# ovtave_up_pcbv1_5.net
KiCad netlist of a schematic drawn in EAGLE
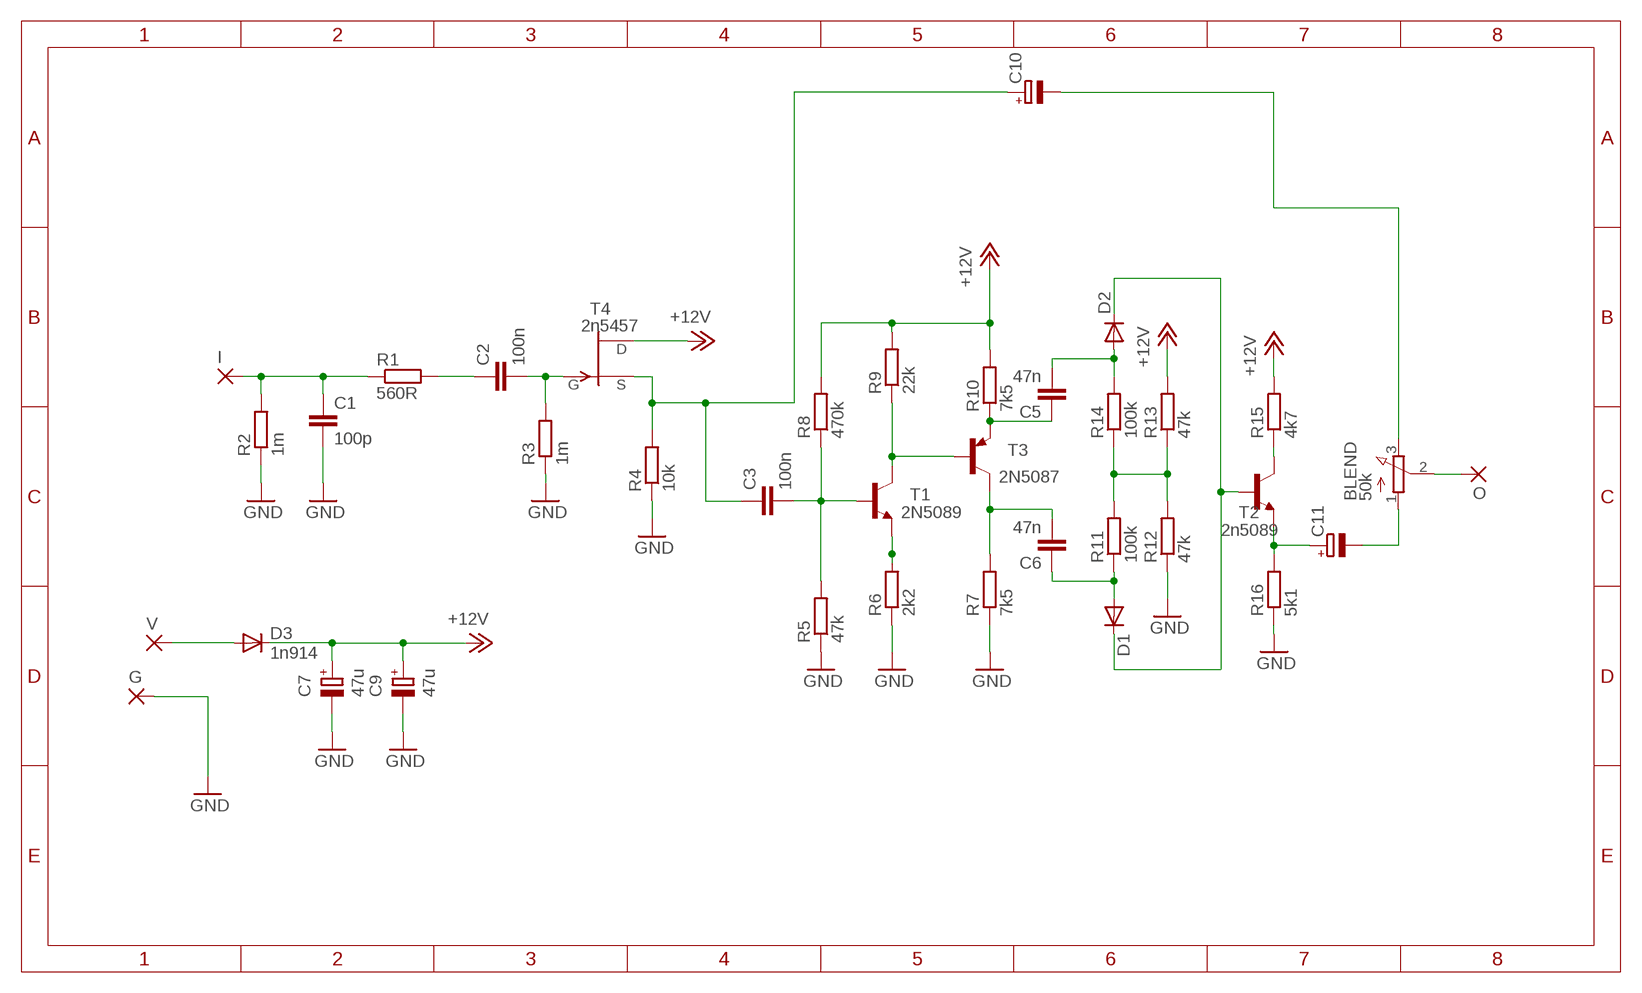
[diagram p0: schematic, sheet 1]

(export (version "E")
  (design (tool "Eeschema 10.0.6"))
  (components
    (comp (ref "BLEND")
      (value "50k")
      (footprint "eagle-import:3RP_1610N")
      (libsource (lib "eagle-import") (part "HEXPOT1"))
    )
    (comp (ref "C1")
      (value "100p")
      (footprint "eagle-import:C5B2.5")
      (libsource (lib "eagle-import") (part "C5/2.5"))
    )
    (comp (ref "C2")
      (value "100n")
      (footprint "eagle-import:C5B2.5")
      (libsource (lib "eagle-import") (part "C5/2.5"))
    )
    (comp (ref "C3")
      (value "100n")
      (footprint "eagle-import:C5B2.5")
      (libsource (lib "eagle-import") (part "C5/2.5"))
    )
    (comp (ref "C5")
      (value "47n")
      (footprint "eagle-import:C5B2.5")
      (libsource (lib "eagle-import") (part "C5/2.5"))
    )
    (comp (ref "C6")
      (value "47n")
      (footprint "eagle-import:C5B2.5")
      (libsource (lib "eagle-import") (part "C5/2.5"))
    )
    (comp (ref "C7")
      (value "47u")
      (footprint "eagle-import:E2-4")
      (libsource (lib "eagle-import") (part "rcl_334_CPOL-EUE2-4"))
    )
    (comp (ref "C9")
      (value "47u")
      (footprint "eagle-import:E2-4")
      (libsource (lib "eagle-import") (part "rcl_334_CPOL-EUE2-4"))
    )
    (comp (ref "C10")
      (value "CPOL-EUE2-4")
      (footprint "eagle-import:E2-4")
      (libsource (lib "eagle-import") (part "CPOL-EUE2-4"))
    )
    (comp (ref "C11")
      (value "CPOL-EUE2-4")
      (footprint "eagle-import:E2-4")
      (libsource (lib "eagle-import") (part "CPOL-EUE2-4"))
    )
    (comp (ref "D1")
      (value "Ge fV match")
      (footprint "eagle-import:DO35-7")
      (libsource (lib "eagle-import") (part "SMALL_DIODEDO35-7"))
    )
    (comp (ref "D2")
      (value "Ge fV match")
      (footprint "eagle-import:DO35-7")
      (libsource (lib "eagle-import") (part "SMALL_DIODEDO35-7"))
    )
    (comp (ref "D3")
      (value "1n914")
      (footprint "eagle-import:DO35-7")
      (libsource (lib "eagle-import") (part "SMALL_DIODEDO35-7"))
    )
    (comp (ref "G")
      (value "1,6/0,9")
      (footprint "eagle-import:1,6_0,9")
      (libsource (lib "eagle-import") (part "1,6/0,9"))
    )
    (comp (ref "I")
      (value "1,6/0,9")
      (footprint "eagle-import:1,6_0,9")
      (libsource (lib "eagle-import") (part "1,6/0,9"))
    )
    (comp (ref "O")
      (value "1,6/0,9")
      (footprint "eagle-import:1,6_0,9")
      (libsource (lib "eagle-import") (part "1,6/0,9"))
    )
    (comp (ref "R1")
      (value "560R")
      (footprint "eagle-import:0207_7")
      (libsource (lib "eagle-import") (part "R-EU_0207/7"))
    )
    (comp (ref "R2")
      (value "1m")
      (footprint "eagle-import:0207_7")
      (libsource (lib "eagle-import") (part "R-EU_0207/7"))
    )
    (comp (ref "R3")
      (value "1m")
      (footprint "eagle-import:0207_7")
      (libsource (lib "eagle-import") (part "R-EU_0207/7"))
    )
    (comp (ref "R4")
      (value "10k")
      (footprint "eagle-import:0207_7")
      (libsource (lib "eagle-import") (part "R-EU_0207/7"))
    )
    (comp (ref "R5")
      (value "47k")
      (footprint "eagle-import:0207_7")
      (libsource (lib "eagle-import") (part "R-EU_0207/7"))
    )
    (comp (ref "R6")
      (value "2k2")
      (footprint "eagle-import:0207_7")
      (libsource (lib "eagle-import") (part "R-EU_0207/7"))
    )
    (comp (ref "R7")
      (value "7k5")
      (footprint "eagle-import:0207_7")
      (libsource (lib "eagle-import") (part "R-EU_0207/7"))
    )
    (comp (ref "R8")
      (value "470k")
      (footprint "eagle-import:0207_7")
      (libsource (lib "eagle-import") (part "R-EU_0207/7"))
    )
    (comp (ref "R9")
      (value "22k")
      (footprint "eagle-import:0207_7")
      (libsource (lib "eagle-import") (part "R-EU_0207/7"))
    )
    (comp (ref "R10")
      (value "7k5")
      (footprint "eagle-import:0207_7")
      (libsource (lib "eagle-import") (part "R-EU_0207/7"))
    )
    (comp (ref "R11")
      (value "100k")
      (footprint "eagle-import:0207_7")
      (libsource (lib "eagle-import") (part "R-EU_0207/7"))
    )
    (comp (ref "R12")
      (value "47k")
      (footprint "eagle-import:0207_7")
      (libsource (lib "eagle-import") (part "R-EU_0207/7"))
    )
    (comp (ref "R13")
      (value "47k")
      (footprint "eagle-import:0207_7")
      (libsource (lib "eagle-import") (part "R-EU_0207/7"))
    )
    (comp (ref "R14")
      (value "100k")
      (footprint "eagle-import:0207_7")
      (libsource (lib "eagle-import") (part "R-EU_0207/7"))
    )
    (comp (ref "R15")
      (value "4k7")
      (footprint "eagle-import:0207_7")
      (libsource (lib "eagle-import") (part "R-EU_0207/7"))
    )
    (comp (ref "R16")
      (value "5k1")
      (footprint "eagle-import:0207_7")
      (libsource (lib "eagle-import") (part "R-EU_0207/7"))
    )
    (comp (ref "T1")
      (value "2N5089")
      (footprint "eagle-import:TO92")
      (libsource (lib "eagle-import") (part "2N5089"))
    )
    (comp (ref "T2")
      (value "2n5089")
      (footprint "eagle-import:TO92")
      (libsource (lib "eagle-import") (part "2N5089"))
    )
    (comp (ref "T3")
      (value "2N5087")
      (footprint "eagle-import:TO92")
      (libsource (lib "eagle-import") (part "2N5087"))
    )
    (comp (ref "T4")
      (value "2n5457")
      (footprint "eagle-import:TO92")
      (libsource (lib "eagle-import") (part "?20J1"))
    )
    (comp (ref "V")
      (value "1,6/0,9")
      (footprint "eagle-import:1,6_0,9")
      (libsource (lib "eagle-import") (part "1,6/0,9"))
    )
  )
  (nets
    (net (code "1") (name "+12V") (class "Default")
      (node (ref "C7") (pin "+") (pinfunction "+_+") (pintype "passive"))
      (node (ref "C9") (pin "+") (pinfunction "+_+") (pintype "passive"))
      (node (ref "D3") (pin "C") (pinfunction "C_C") (pintype "passive"))
      (node (ref "R10") (pin "2") (pinfunction "2_2") (pintype "passive"))
      (node (ref "R13") (pin "2") (pinfunction "2_2") (pintype "passive"))
      (node (ref "R15") (pin "2") (pinfunction "2_2") (pintype "passive"))
      (node (ref "R8") (pin "2") (pinfunction "2_2") (pintype "passive"))
      (node (ref "R9") (pin "2") (pinfunction "2_2") (pintype "passive"))
      (node (ref "T4") (pin "3") (pinfunction "D_3") (pintype "passive"))
    )
    (net (code "2") (name "GND") (class "Default")
      (node (ref "C1") (pin "2") (pinfunction "2_2") (pintype "passive"))
      (node (ref "C7") (pin "-") (pinfunction "-_-") (pintype "passive"))
      (node (ref "C9") (pin "-") (pinfunction "-_-") (pintype "passive"))
      (node (ref "G") (pin "1") (pinfunction "P_1") (pintype "passive"))
      (node (ref "R12") (pin "1") (pinfunction "1_1") (pintype "passive"))
      (node (ref "R16") (pin "1") (pinfunction "1_1") (pintype "passive"))
      (node (ref "R2") (pin "1") (pinfunction "1_1") (pintype "passive"))
      (node (ref "R3") (pin "1") (pinfunction "1_1") (pintype "passive"))
      (node (ref "R4") (pin "1") (pinfunction "1_1") (pintype "passive"))
      (node (ref "R5") (pin "1") (pinfunction "1_1") (pintype "passive"))
      (node (ref "R6") (pin "1") (pinfunction "1_1") (pintype "passive"))
      (node (ref "R7") (pin "1") (pinfunction "1_1") (pintype "passive"))
    )
    (net (code "3") (name "Net-(BLEND-A)") (class "Default")
      (node (ref "BLEND") (pin "1") (pinfunction "A_1") (pintype "passive"))
      (node (ref "C11") (pin "-") (pinfunction "-_-") (pintype "passive"))
    )
    (net (code "4") (name "Net-(BLEND-E)") (class "Default")
      (node (ref "BLEND") (pin "3") (pinfunction "E_3") (pintype "passive"))
      (node (ref "C10") (pin "-") (pinfunction "-_-") (pintype "passive"))
    )
    (net (code "5") (name "Net-(BLEND-S)") (class "Default")
      (node (ref "BLEND") (pin "2") (pinfunction "S_2") (pintype "passive"))
      (node (ref "O") (pin "1") (pinfunction "P_1") (pintype "passive"))
    )
    (net (code "6") (name "Net-(C2-Pad1)") (class "Default")
      (node (ref "C2") (pin "1") (pinfunction "1_1") (pintype "passive"))
      (node (ref "R1") (pin "2") (pinfunction "2_2") (pintype "passive"))
    )
    (net (code "7") (name "Net-(C5-Pad2)") (class "Default")
      (node (ref "C5") (pin "2") (pinfunction "2_2") (pintype "passive"))
      (node (ref "D2") (pin "A") (pinfunction "A_A") (pintype "passive"))
      (node (ref "R14") (pin "2") (pinfunction "2_2") (pintype "passive"))
    )
    (net (code "8") (name "Net-(C6-Pad1)") (class "Default")
      (node (ref "C6") (pin "1") (pinfunction "1_1") (pintype "passive"))
      (node (ref "D1") (pin "A") (pinfunction "A_A") (pintype "passive"))
      (node (ref "R11") (pin "1") (pinfunction "1_1") (pintype "passive"))
    )
    (net (code "9") (name "Net-(I-P)") (class "Default")
      (node (ref "C1") (pin "1") (pinfunction "1_1") (pintype "passive"))
      (node (ref "I") (pin "1") (pinfunction "P_1") (pintype "passive"))
      (node (ref "R1") (pin "1") (pinfunction "1_1") (pintype "passive"))
      (node (ref "R2") (pin "2") (pinfunction "2_2") (pintype "passive"))
    )
    (net (code "10") (name "Net-(R11-Pad2)") (class "Default")
      (node (ref "R11") (pin "2") (pinfunction "2_2") (pintype "passive"))
      (node (ref "R12") (pin "2") (pinfunction "2_2") (pintype "passive"))
      (node (ref "R13") (pin "1") (pinfunction "1_1") (pintype "passive"))
      (node (ref "R14") (pin "1") (pinfunction "1_1") (pintype "passive"))
    )
    (net (code "11") (name "Net-(T1-B)") (class "Default")
      (node (ref "C3") (pin "2") (pinfunction "2_2") (pintype "passive"))
      (node (ref "R5") (pin "2") (pinfunction "2_2") (pintype "passive"))
      (node (ref "R8") (pin "1") (pinfunction "1_1") (pintype "passive"))
      (node (ref "T1") (pin "2") (pinfunction "B_2") (pintype "passive"))
    )
    (net (code "12") (name "Net-(T1-C)") (class "Default")
      (node (ref "R9") (pin "1") (pinfunction "1_1") (pintype "passive"))
      (node (ref "T1") (pin "1") (pinfunction "C_1") (pintype "passive"))
      (node (ref "T3") (pin "2") (pinfunction "B_2") (pintype "passive"))
    )
    (net (code "13") (name "Net-(T1-E)") (class "Default")
      (node (ref "R6") (pin "2") (pinfunction "2_2") (pintype "passive"))
      (node (ref "T1") (pin "3") (pinfunction "E_3") (pintype "passive"))
    )
    (net (code "14") (name "Net-(T2-B)") (class "Default")
      (node (ref "D1") (pin "C") (pinfunction "C_C") (pintype "passive"))
      (node (ref "D2") (pin "C") (pinfunction "C_C") (pintype "passive"))
      (node (ref "T2") (pin "2") (pinfunction "B_2") (pintype "passive"))
    )
    (net (code "15") (name "Net-(T2-C)") (class "Default")
      (node (ref "R15") (pin "1") (pinfunction "1_1") (pintype "passive"))
      (node (ref "T2") (pin "1") (pinfunction "C_1") (pintype "passive"))
    )
    (net (code "16") (name "Net-(T2-E)") (class "Default")
      (node (ref "C11") (pin "+") (pinfunction "+_+") (pintype "passive"))
      (node (ref "R16") (pin "2") (pinfunction "2_2") (pintype "passive"))
      (node (ref "T2") (pin "3") (pinfunction "E_3") (pintype "passive"))
    )
    (net (code "17") (name "Net-(T3-C)") (class "Default")
      (node (ref "C6") (pin "2") (pinfunction "2_2") (pintype "passive"))
      (node (ref "R7") (pin "2") (pinfunction "2_2") (pintype "passive"))
      (node (ref "T3") (pin "1") (pinfunction "C_1") (pintype "passive"))
    )
    (net (code "18") (name "Net-(T3-E)") (class "Default")
      (node (ref "C5") (pin "1") (pinfunction "1_1") (pintype "passive"))
      (node (ref "R10") (pin "1") (pinfunction "1_1") (pintype "passive"))
      (node (ref "T3") (pin "3") (pinfunction "E_3") (pintype "passive"))
    )
    (net (code "19") (name "Net-(T4-G)") (class "Default")
      (node (ref "C2") (pin "2") (pinfunction "2_2") (pintype "passive"))
      (node (ref "R3") (pin "2") (pinfunction "2_2") (pintype "passive"))
      (node (ref "T4") (pin "1") (pinfunction "G_1") (pintype "passive"))
    )
    (net (code "20") (name "Net-(T4-S)") (class "Default")
      (node (ref "C10") (pin "+") (pinfunction "+_+") (pintype "passive"))
      (node (ref "C3") (pin "1") (pinfunction "1_1") (pintype "passive"))
      (node (ref "R4") (pin "2") (pinfunction "2_2") (pintype "passive"))
      (node (ref "T4") (pin "2") (pinfunction "S_2") (pintype "passive"))
    )
    (net (code "21") (name "Net-(V-P)") (class "Default")
      (node (ref "D3") (pin "A") (pinfunction "A_A") (pintype "passive"))
      (node (ref "V") (pin "1") (pinfunction "P_1") (pintype "passive"))
    )
  )
)
